# esp32.net
KiCad netlist of a schematic drawn in EAGLE
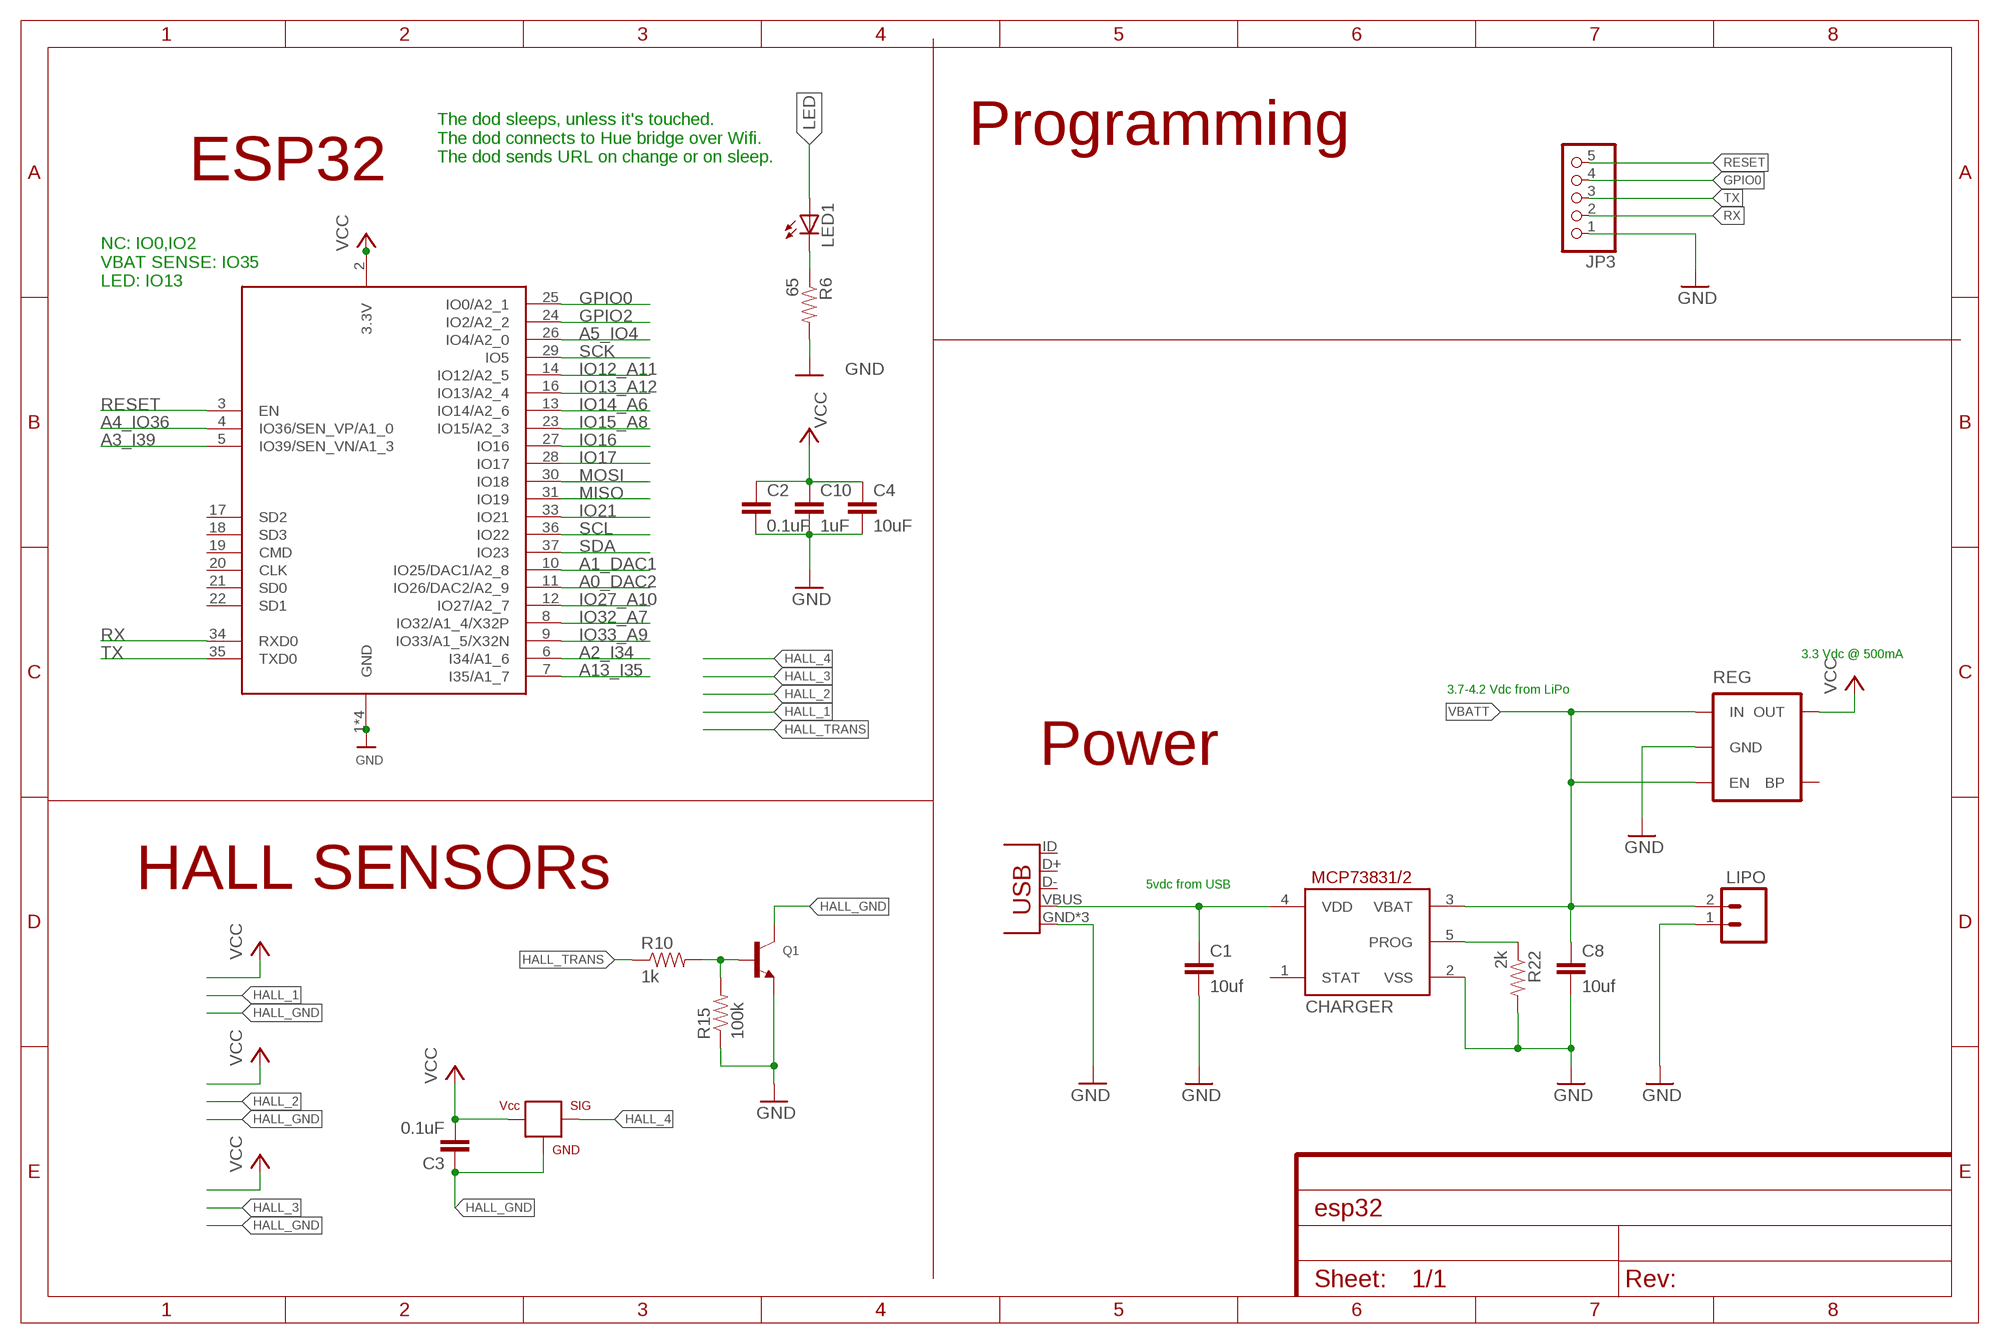
[diagram p0: schematic, sheet 1]

(export (version "E")
  (design (tool "Eeschema 10.0.6"))
  (components
    (comp (ref "C1")
      (value "10uf")
      (footprint "eagle-import:0603-CAP")
      (libsource (lib "eagle-import") (part "SparkFun-Capacitors_CAP0603-CAP"))
    )
    (comp (ref "C2")
      (value "0.1uF")
      (footprint "eagle-import:0402-CAP")
      (libsource (lib "eagle-import") (part "CAP0402-CAP"))
    )
    (comp (ref "C3")
      (value "0.1uF")
      (footprint "eagle-import:0603-CAP")
      (libsource (lib "eagle-import") (part "CAP0603-CAP"))
    )
    (comp (ref "C4")
      (value "10uF")
      (footprint "eagle-import:0402-CAP")
      (libsource (lib "eagle-import") (part "CAP0402-CAP"))
    )
    (comp (ref "C8")
      (value "10uf")
      (footprint "eagle-import:0603-CAP")
      (libsource (lib "eagle-import") (part "SparkFun-Capacitors_CAP0603-CAP"))
    )
    (comp (ref "C10")
      (value "1uF")
      (footprint "eagle-import:0402-CAP")
      (libsource (lib "eagle-import") (part "CAP0402-CAP"))
    )
    (comp (ref "CHARGER")
      (value "MCP73831/OT")
      (footprint "eagle-import:SOT23-5L")
      (libsource (lib "eagle-import") (part "MCP73831/OT"))
    )
    (comp (ref "HALL")
      (value "HALLEFFECT-A1326")
      (footprint "eagle-import:SOT23-3")
      (libsource (lib "eagle-import") (part "HALLEFFECT-A1326"))
    )
    (comp (ref "JP1")
      (value "USB-MICROB")
      (footprint "eagle-import:USB-MICROB")
      (libsource (lib "eagle-import") (part "USB-MICROB"))
    )
    (comp (ref "JP3")
      (value "PINHD-1X55X2MM")
      (footprint "eagle-import:1_05X2MM")
      (libsource (lib "eagle-import") (part "PINHD-1X55X2MM"))
    )
    (comp (ref "LED1")
      (value "LEDCHIPLED_0603")
      (footprint "eagle-import:CHIPLED_0603")
      (libsource (lib "eagle-import") (part "LEDCHIPLED_0603"))
    )
    (comp (ref "LIPO")
      (value "M02")
      (footprint "eagle-import:1X02_LONGPADS")
      (libsource (lib "eagle-import") (part "M02"))
    )
    (comp (ref "Q1")
      (value "TRANSISTOR_NPN")
      (footprint "eagle-import:SOT-23-R")
      (libsource (lib "eagle-import") (part "TRANSISTOR_NPN"))
    )
    (comp (ref "R6")
      (value "65")
      (footprint "eagle-import:0805")
      (libsource (lib "eagle-import") (part "SparkFun-Resistors_RESISTOR0805-RES"))
    )
    (comp (ref "R10")
      (value "1k")
      (footprint "eagle-import:0402-RES")
      (libsource (lib "eagle-import") (part "RESISTOR0402-RES"))
    )
    (comp (ref "R15")
      (value "100k")
      (footprint "eagle-import:0402-RES")
      (libsource (lib "eagle-import") (part "RESISTOR0402-RES"))
    )
    (comp (ref "R22")
      (value "2k")
      (footprint "eagle-import:0402-RES")
      (libsource (lib "eagle-import") (part "RESISTOR0402-RES"))
    )
    (comp (ref "REG")
      (value "MIC52053.3V")
      (footprint "eagle-import:SOT23-5")
      (libsource (lib "eagle-import") (part "MIC52053.3V"))
    )
    (comp (ref "X2")
      (value "ESP32_WROOM32_SKINNY")
      (footprint "eagle-import:WROOM32_SKINNY")
      (libsource (lib "eagle-import") (part "ESP32_WROOM32_SKINNY"))
    )
  )
  (nets
    (net (code "1") (name "/A0_DAC2") (class "Default")
      (node (ref "X2") (pin "11") (pinfunction "IO26/DAC2/A2_9_11") (pintype "bidirectional"))
    )
    (net (code "2") (name "/A1_DAC1") (class "Default")
      (node (ref "X2") (pin "10") (pinfunction "IO25/DAC1/A2_8_10") (pintype "bidirectional"))
    )
    (net (code "3") (name "/A2_I34") (class "Default")
      (node (ref "X2") (pin "6") (pinfunction "I34/A1_6_6") (pintype "bidirectional"))
    )
    (net (code "4") (name "/A3_I39") (class "Default")
      (node (ref "X2") (pin "5") (pinfunction "IO39/SEN_VN/A1_3_5") (pintype "passive"))
    )
    (net (code "5") (name "/A4_IO36") (class "Default")
      (node (ref "X2") (pin "4") (pinfunction "IO36/SEN_VP/A1_0_4") (pintype "passive"))
    )
    (net (code "6") (name "/A5_IO4") (class "Default")
      (node (ref "X2") (pin "26") (pinfunction "IO4/A2_0_26") (pintype "bidirectional"))
    )
    (net (code "7") (name "/A13_I35") (class "Default")
      (node (ref "X2") (pin "7") (pinfunction "I35/A1_7_7") (pintype "bidirectional"))
    )
    (net (code "8") (name "/GPIO2") (class "Default")
      (node (ref "X2") (pin "24") (pinfunction "IO2/A2_2_24") (pintype "bidirectional"))
    )
    (net (code "9") (name "/IO12_A11") (class "Default")
      (node (ref "X2") (pin "14") (pinfunction "IO12/A2_5_14") (pintype "bidirectional"))
    )
    (net (code "10") (name "/IO13_A12") (class "Default")
      (node (ref "X2") (pin "16") (pinfunction "IO13/A2_4_16") (pintype "bidirectional"))
    )
    (net (code "11") (name "/IO14_A6") (class "Default")
      (node (ref "X2") (pin "13") (pinfunction "IO14/A2_6_13") (pintype "bidirectional"))
    )
    (net (code "12") (name "/IO15_A8") (class "Default")
      (node (ref "X2") (pin "23") (pinfunction "IO15/A2_3_23") (pintype "bidirectional"))
    )
    (net (code "13") (name "/IO16") (class "Default")
      (node (ref "X2") (pin "27") (pinfunction "IO16_27") (pintype "bidirectional"))
    )
    (net (code "14") (name "/IO17") (class "Default")
      (node (ref "X2") (pin "28") (pinfunction "IO17_28") (pintype "bidirectional"))
    )
    (net (code "15") (name "/IO21") (class "Default")
      (node (ref "X2") (pin "33") (pinfunction "IO21_33") (pintype "bidirectional"))
    )
    (net (code "16") (name "/IO27_A10") (class "Default")
      (node (ref "X2") (pin "12") (pinfunction "IO27/A2_7_12") (pintype "bidirectional"))
    )
    (net (code "17") (name "/IO32_A7") (class "Default")
      (node (ref "X2") (pin "8") (pinfunction "IO32/A1_4/X32P_8") (pintype "bidirectional"))
    )
    (net (code "18") (name "/IO33_A9") (class "Default")
      (node (ref "X2") (pin "9") (pinfunction "IO33/A1_5/X32N_9") (pintype "bidirectional"))
    )
    (net (code "19") (name "/MISO") (class "Default")
      (node (ref "X2") (pin "31") (pinfunction "IO19_31") (pintype "bidirectional"))
    )
    (net (code "20") (name "/MOSI") (class "Default")
      (node (ref "X2") (pin "30") (pinfunction "IO18_30") (pintype "bidirectional"))
    )
    (net (code "21") (name "/SCK") (class "Default")
      (node (ref "X2") (pin "29") (pinfunction "IO5_29") (pintype "bidirectional"))
    )
    (net (code "22") (name "/SCL") (class "Default")
      (node (ref "X2") (pin "36") (pinfunction "IO22_36") (pintype "bidirectional"))
    )
    (net (code "23") (name "/SDA") (class "Default")
      (node (ref "X2") (pin "37") (pinfunction "IO23_37") (pintype "bidirectional"))
    )
    (net (code "24") (name "GND") (class "Default")
      (node (ref "C1") (pin "2") (pinfunction "2_2") (pintype "passive"))
      (node (ref "C10") (pin "2") (pinfunction "2_2") (pintype "passive"))
      (node (ref "C2") (pin "2") (pinfunction "2_2") (pintype "passive"))
      (node (ref "C4") (pin "2") (pinfunction "2_2") (pintype "passive"))
      (node (ref "C8") (pin "2") (pinfunction "2_2") (pintype "passive"))
      (node (ref "CHARGER") (pin "2") (pinfunction "VSS_2") (pintype "power_in"))
      (node (ref "JP1") (pin "GND") (pinfunction "GND_GND") (pintype "bidirectional"))
      (node (ref "JP1") (pin "MT1") (pinfunction "GND_MT1") (pintype "bidirectional"))
      (node (ref "JP1") (pin "MT2") (pinfunction "GND_MT2") (pintype "bidirectional"))
      (node (ref "JP3") (pin "1") (pinfunction "1_1") (pintype "passive"))
      (node (ref "LIPO") (pin "1") (pinfunction "1_1") (pintype "passive"))
      (node (ref "Q1") (pin "3-EMITTER") (pinfunction "E_3-EMITTER") (pintype "passive"))
      (node (ref "R15") (pin "1") (pinfunction "1_1") (pintype "passive"))
      (node (ref "R22") (pin "2") (pinfunction "2_2") (pintype "passive"))
      (node (ref "R6") (pin "2") (pinfunction "2_2") (pintype "passive"))
      (node (ref "REG") (pin "2") (pinfunction "GND_2") (pintype "input"))
      (node (ref "X2") (pin "1") (pinfunction "GND_1") (pintype "passive"))
      (node (ref "X2") (pin "15") (pinfunction "GND_15") (pintype "passive"))
      (node (ref "X2") (pin "38") (pinfunction "GND_38") (pintype "passive"))
      (node (ref "X2") (pin "P$1") (pinfunction "GND_P$1") (pintype "passive"))
    )
    (net (code "25") (name "GPIO0") (class "Default")
      (node (ref "JP3") (pin "4") (pinfunction "4_4") (pintype "passive"))
      (node (ref "X2") (pin "25") (pinfunction "IO0/A2_1_25") (pintype "bidirectional"))
    )
    (net (code "29") (name "HALL_4") (class "Default")
      (node (ref "HALL") (pin "2") (pinfunction "SIG_2") (pintype "bidirectional"))
    )
    (net (code "30") (name "HALL_GND") (class "Default")
      (node (ref "C3") (pin "1") (pinfunction "1_1") (pintype "passive"))
      (node (ref "HALL") (pin "3") (pinfunction "GND_3") (pintype "bidirectional"))
      (node (ref "Q1") (pin "2-COLLECTOR") (pinfunction "C_2-COLLECTOR") (pintype "passive"))
    )
    (net (code "31") (name "HALL_TRANS") (class "Default")
      (node (ref "R10") (pin "1") (pinfunction "1_1") (pintype "passive"))
    )
    (net (code "32") (name "LED") (class "Default")
      (node (ref "LED1") (pin "A") (pinfunction "A_A") (pintype "passive"))
    )
    (net (code "33") (name "Net-(CHARGER-PROG)") (class "Default")
      (node (ref "CHARGER") (pin "5") (pinfunction "PROG_5") (pintype "input"))
      (node (ref "R22") (pin "1") (pinfunction "1_1") (pintype "passive"))
    )
    (net (code "34") (name "Net-(CHARGER-VDD)") (class "Default")
      (node (ref "C1") (pin "1") (pinfunction "1_1") (pintype "passive"))
      (node (ref "CHARGER") (pin "4") (pinfunction "VDD_4") (pintype "power_in"))
      (node (ref "JP1") (pin "VBUS") (pinfunction "VBUS_VBUS") (pintype "bidirectional"))
    )
    (net (code "35") (name "Net-(LED1-PadC)") (class "Default")
      (node (ref "LED1") (pin "C") (pinfunction "C_C") (pintype "passive"))
      (node (ref "R6") (pin "1") (pinfunction "1_1") (pintype "passive"))
    )
    (net (code "36") (name "Net-(Q1-B)") (class "Default")
      (node (ref "Q1") (pin "1-BASE") (pinfunction "B_1-BASE") (pintype "passive"))
      (node (ref "R10") (pin "2") (pinfunction "2_2") (pintype "passive"))
      (node (ref "R15") (pin "2") (pinfunction "2_2") (pintype "passive"))
    )
    (net (code "37") (name "RESET") (class "Default")
      (node (ref "JP3") (pin "5") (pinfunction "5_5") (pintype "passive"))
      (node (ref "X2") (pin "3") (pinfunction "EN_3") (pintype "input"))
    )
    (net (code "38") (name "RX") (class "Default")
      (node (ref "JP3") (pin "2") (pinfunction "2_2") (pintype "passive"))
      (node (ref "X2") (pin "34") (pinfunction "RXD0_34") (pintype "input"))
    )
    (net (code "39") (name "TX") (class "Default")
      (node (ref "JP3") (pin "3") (pinfunction "3_3") (pintype "passive"))
      (node (ref "X2") (pin "35") (pinfunction "TXD0_35") (pintype "output"))
    )
    (net (code "40") (name "VBATT") (class "Default")
      (node (ref "C8") (pin "1") (pinfunction "1_1") (pintype "passive"))
      (node (ref "CHARGER") (pin "3") (pinfunction "VBAT_3") (pintype "bidirectional"))
      (node (ref "LIPO") (pin "2") (pinfunction "2_2") (pintype "passive"))
      (node (ref "REG") (pin "1") (pinfunction "IN_1") (pintype "input"))
      (node (ref "REG") (pin "3") (pinfunction "EN_3") (pintype "input"))
    )
    (net (code "41") (name "VCC") (class "Default")
      (node (ref "C10") (pin "1") (pinfunction "1_1") (pintype "passive"))
      (node (ref "C2") (pin "1") (pinfunction "1_1") (pintype "passive"))
      (node (ref "C3") (pin "2") (pinfunction "2_2") (pintype "passive"))
      (node (ref "C4") (pin "1") (pinfunction "1_1") (pintype "passive"))
      (node (ref "HALL") (pin "1") (pinfunction "VCC_1") (pintype "bidirectional"))
      (node (ref "REG") (pin "5") (pinfunction "OUT_5") (pintype "passive"))
      (node (ref "X2") (pin "2") (pinfunction "3.3V_2") (pintype "passive"))
    )
    (net (code "42") (name "unconnected-(CHARGER-STAT-Pad1)") (class "Default")
      (node (ref "CHARGER") (pin "1") (pinfunction "STAT_1") (pintype "output"))
    )
    (net (code "43") (name "unconnected-(JP1-PadD+)") (class "Default")
      (node (ref "JP1") (pin "D+") (pinfunction "D+_D+") (pintype "bidirectional"))
    )
    (net (code "44") (name "unconnected-(JP1-PadD-)") (class "Default")
      (node (ref "JP1") (pin "D-") (pinfunction "D-_D-") (pintype "bidirectional"))
    )
    (net (code "45") (name "unconnected-(JP1-SHIELD-PadID)") (class "Default")
      (node (ref "JP1") (pin "ID") (pinfunction "SHIELD_ID") (pintype "bidirectional"))
    )
    (net (code "46") (name "unconnected-(REG-BP-Pad4)") (class "Default")
      (node (ref "REG") (pin "4") (pinfunction "BP_4") (pintype "input"))
    )
    (net (code "47") (name "unconnected-(X2-CLK-Pad20)") (class "Default")
      (node (ref "X2") (pin "20") (pinfunction "CLK_20") (pintype "bidirectional"))
    )
    (net (code "48") (name "unconnected-(X2-CMD-Pad19)") (class "Default")
      (node (ref "X2") (pin "19") (pinfunction "CMD_19") (pintype "bidirectional"))
    )
    (net (code "49") (name "unconnected-(X2-SD0-Pad21)") (class "Default")
      (node (ref "X2") (pin "21") (pinfunction "SD0_21") (pintype "bidirectional"))
    )
    (net (code "50") (name "unconnected-(X2-SD1-Pad22)") (class "Default")
      (node (ref "X2") (pin "22") (pinfunction "SD1_22") (pintype "bidirectional"))
    )
    (net (code "51") (name "unconnected-(X2-SD2-Pad17)") (class "Default")
      (node (ref "X2") (pin "17") (pinfunction "SD2_17") (pintype "bidirectional"))
    )
    (net (code "52") (name "unconnected-(X2-SD3-Pad18)") (class "Default")
      (node (ref "X2") (pin "18") (pinfunction "SD3_18") (pintype "bidirectional"))
    )
  )
)
